# PX4FMUv2_4_6_04.net
KiCad netlist of a schematic drawn in Altium Designer
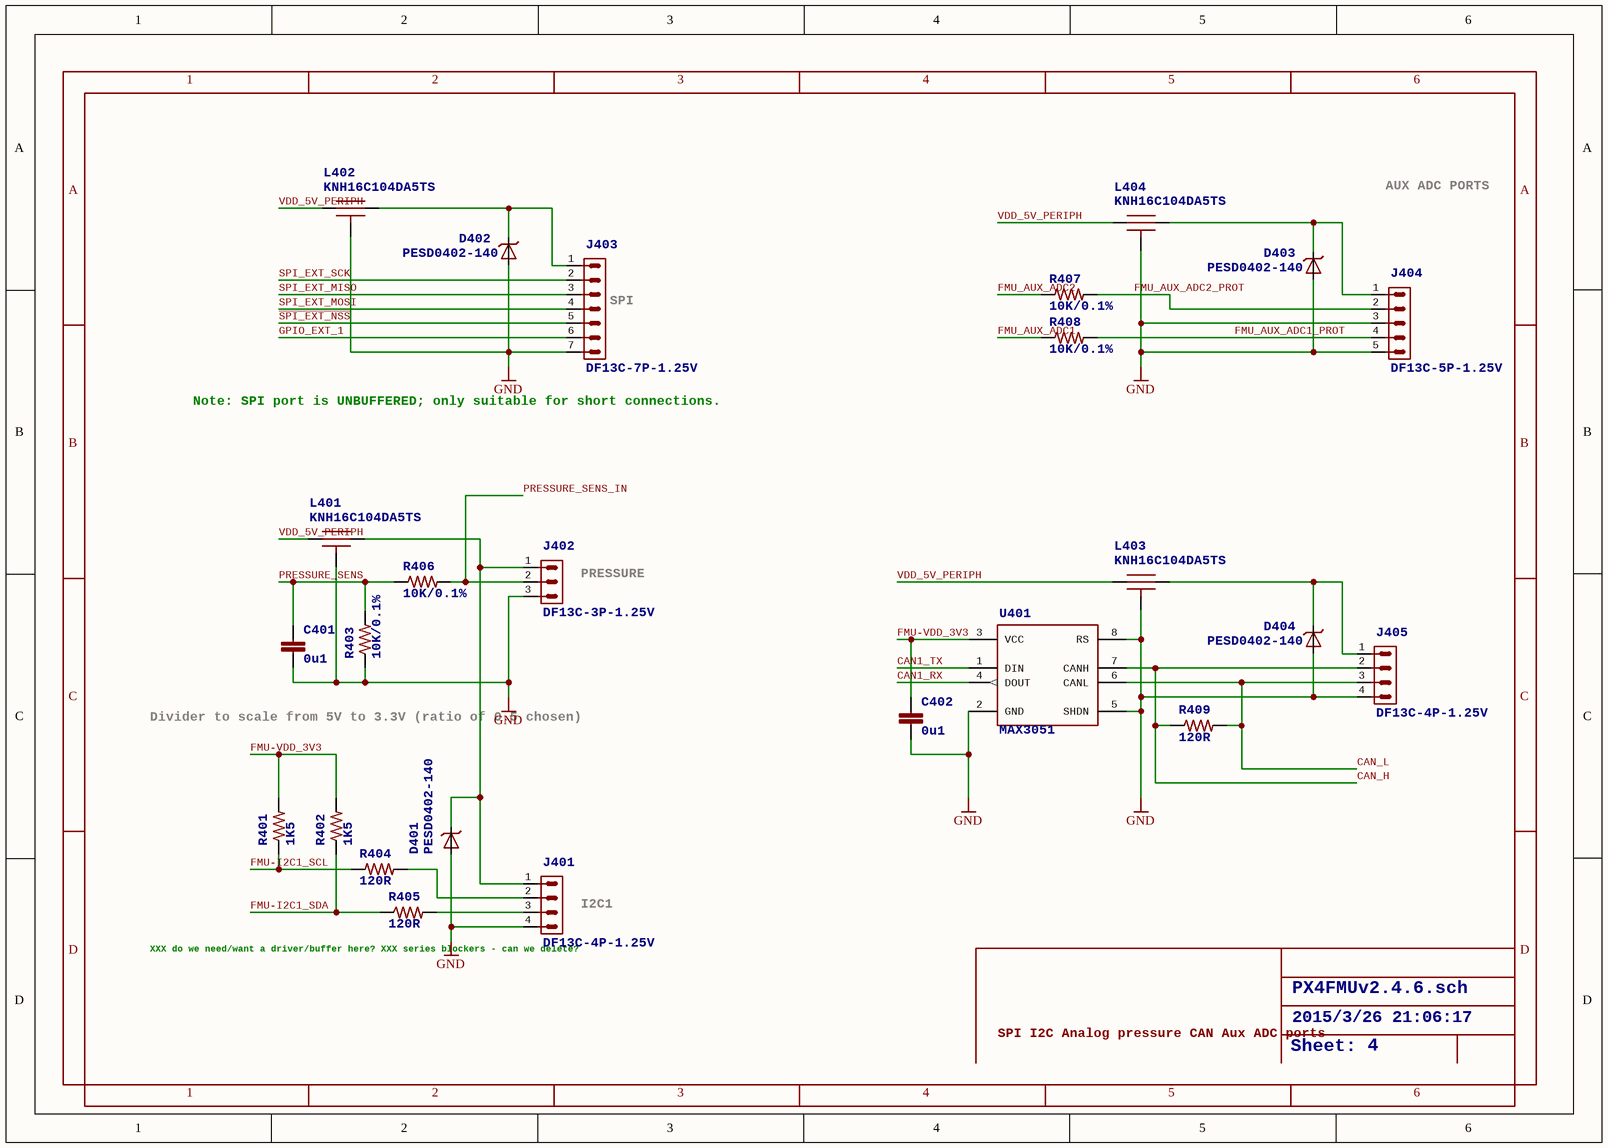
[diagram p0: PX4FMUv2.4.6_04.SchDoc]

(export (version "E")
  (design (tool "Eeschema 10.0.6"))
  (components
    (comp (ref "C401")
      (value "0u1")
      (footprint "0402-CAP")
      (description "<b>Capacitor</b>\nStandard 0603 ceramic capacitor, and 0.1\" leaded capacitor.")
      (fields (field (name "PARTNO") "CC0402ZRY5V7BB104"))
      (libsource (lib "pixhawk2") (part "CAP0402"))
    )
    (comp (ref "C402")
      (value "0u1")
      (footprint "0402-CAP")
      (description "<b>Capacitor</b>\nStandard 0603 ceramic capacitor, and 0.1\" leaded capacitor.")
      (fields (field (name "PARTNO") "CC0402ZRY5V7BB104"))
      (libsource (lib "pixhawk2") (part "CAP0402"))
    )
    (comp (ref "D401")
      (value "PESD0402-140")
      (footprint "0402-TVS")
      (libsource (lib "pixhawk2") (part "DIODE-TVS"))
    )
    (comp (ref "D402")
      (value "PESD0402-140")
      (footprint "0402-TVS")
      (libsource (lib "pixhawk2") (part "DIODE-TVS"))
    )
    (comp (ref "D403")
      (value "PESD0402-140")
      (footprint "0402-TVS")
      (libsource (lib "pixhawk2") (part "DIODE-TVS"))
    )
    (comp (ref "D404")
      (value "PESD0402-140")
      (footprint "0402-TVS")
      (libsource (lib "pixhawk2") (part "DIODE-TVS"))
    )
    (comp (ref "J401")
      (value "DF13C-4P-1.25V")
      (footprint "DF13C-4P-1.25V")
      (description "DF13-4P\n1.25mm Pitch Miniature Crimping Connector.")
      (fields (field (name "PARTNO") "DF13C-4P-1.25V(20)"))
      (libsource (lib "con-hirose-df13") (part "DF13-4P-1.25V"))
    )
    (comp (ref "J402")
      (value "DF13C-3P-1.25V")
      (footprint "DF13C-3P-1.25V")
      (description "DF13-3P\n1.25mm Pitch Miniature Crimping Connector.")
      (fields (field (name "PARTNO") "DF13C-3P-1.25V(20)"))
      (libsource (lib "con-hirose-df13") (part "DF13-3P-1.25V"))
    )
    (comp (ref "J403")
      (value "DF13C-7P-1.25V")
      (footprint "DF13C-7P-1.25V")
      (description "DF13-7P\n1.25mm Pitch Miniature Crimping Connector.")
      (fields (field (name "PARTNO") "DF13C-7P-1.25V(20)"))
      (libsource (lib "con-hirose-df13") (part "DF13-7P-1.25V"))
    )
    (comp (ref "J404")
      (value "DF13C-5P-1.25V")
      (footprint "DF13C-5P-1.25V")
      (description "DF13-5P\n1.25mm Pitch Miniature Crimping Connector.")
      (fields (field (name "PARTNO") "DF13C-5P-1.25V(20)"))
      (libsource (lib "con-hirose-df13") (part "DF13-5P-1.25V"))
    )
    (comp (ref "J405")
      (value "DF13C-4P-1.25V")
      (footprint "DF13C-4P-1.25V")
      (description "DF13-4P\n1.25mm Pitch Miniature Crimping Connector.")
      (fields (field (name "PARTNO") "DF13C-4P-1.25V(20)"))
      (libsource (lib "con-hirose-df13") (part "DF13-4P-1.25V"))
    )
    (comp (ref "L401")
      (value "KNH16C104DA5TS")
      (footprint "KYOCERA-KNH16-DA")
      (description "Kyocera KNH16C104DA5TS EMI filter")
      (libsource (lib "pixhawk2") (part "KNH16C104DA5TS"))
    )
    (comp (ref "L402")
      (value "KNH16C104DA5TS")
      (footprint "KYOCERA-KNH16-DA")
      (description "Kyocera KNH16C104DA5TS EMI filter")
      (libsource (lib "pixhawk2") (part "KNH16C104DA5TS"))
    )
    (comp (ref "L403")
      (value "KNH16C104DA5TS")
      (footprint "KYOCERA-KNH16-DA")
      (description "Kyocera KNH16C104DA5TS EMI filter")
      (libsource (lib "pixhawk2") (part "KNH16C104DA5TS"))
    )
    (comp (ref "L404")
      (value "KNH16C104DA5TS")
      (footprint "KYOCERA-KNH16-DA")
      (description "Kyocera KNH16C104DA5TS EMI filter")
      (libsource (lib "pixhawk2") (part "KNH16C104DA5TS"))
    )
    (comp (ref "R401")
      (value "1K5")
      (footprint "0402-RES")
      (fields (field (name "PARTNO") "RC0402FR-071K5L"))
      (libsource (lib "pixhawk2") (part "RESISTOR0402-RES"))
    )
    (comp (ref "R402")
      (value "1K5")
      (footprint "0402-RES")
      (fields (field (name "PARTNO") "RC0402FR-071K5L"))
      (libsource (lib "pixhawk2") (part "RESISTOR0402-RES"))
    )
    (comp (ref "R403")
      (value "10K/0.1%")
      (footprint "0402-RES")
      (fields (field (name "PARTNO") "ERA-2AEB103X"))
      (libsource (lib "pixhawk2") (part "RESISTOR0402-RES"))
    )
    (comp (ref "R404")
      (value "120R")
      (footprint "0402-RES")
      (fields (field (name "PARTNO") "RC0402FR-07120RL"))
      (libsource (lib "pixhawk2") (part "RESISTOR0402-RES"))
    )
    (comp (ref "R405")
      (value "120R")
      (footprint "0402-RES")
      (fields (field (name "PARTNO") "RC0402FR-07120RL"))
      (libsource (lib "pixhawk2") (part "RESISTOR0402-RES"))
    )
    (comp (ref "R406")
      (value "10K/0.1%")
      (footprint "0402-RES")
      (fields (field (name "PARTNO") "ERA-2AEB103X"))
      (libsource (lib "pixhawk2") (part "RESISTOR0402-RES"))
    )
    (comp (ref "R407")
      (value "10K/0.1%")
      (footprint "0402-RES")
      (fields (field (name "PARTNO") "ERA-2AEB103X"))
      (libsource (lib "pixhawk2") (part "RESISTOR0402-RES"))
    )
    (comp (ref "R408")
      (value "10K/0.1%")
      (footprint "0402-RES")
      (fields (field (name "PARTNO") "ERA-2AEB103X"))
      (libsource (lib "pixhawk2") (part "RESISTOR0402-RES"))
    )
    (comp (ref "R409")
      (value "120R")
      (footprint "0402-RES")
      (fields (field (name "PARTNO") "RC0402FR-07120RL"))
      (libsource (lib "pixhawk2") (part "RESISTOR0402-RES"))
    )
    (comp (ref "U401")
      (value "MAX3051")
      (footprint "SOT23-8")
      (description "3.3-V CAN TRANSCEIVER")
      (fields (field (name "PARTNO") "MAX3051EKA"))
      (libsource (lib "pixhawk2") (part "MAX3051MAX3051EKA"))
    )
  )
  (nets
    (net (code "1") (name "/CAN1_RX") (class "Default")
      (node (ref "U401") (pin "4") (pinfunction "DOUT_4") (pintype "output"))
    )
    (net (code "2") (name "/CAN1_TX") (class "Default")
      (node (ref "U401") (pin "1") (pinfunction "DIN_1") (pintype "passive"))
    )
    (net (code "3") (name "/CAN_H") (class "Default")
      (node (ref "J405") (pin "2") (pinfunction "2_2") (pintype "passive"))
      (node (ref "R409") (pin "P$1") (pinfunction "1_P$1") (pintype "passive"))
      (node (ref "U401") (pin "7") (pinfunction "CANH_7") (pintype "passive"))
    )
    (net (code "4") (name "/CAN_L") (class "Default")
      (node (ref "J405") (pin "3") (pinfunction "3_3") (pintype "passive"))
      (node (ref "R409") (pin "P$2") (pinfunction "2_P$2") (pintype "passive"))
      (node (ref "U401") (pin "6") (pinfunction "CANL_6") (pintype "passive"))
    )
    (net (code "5") (name "/FMU-I2C1_SCL") (class "Default")
      (node (ref "R401") (pin "P$1") (pinfunction "1_P$1") (pintype "passive"))
      (node (ref "R404") (pin "P$1") (pinfunction "1_P$1") (pintype "passive"))
    )
    (net (code "6") (name "/FMU-I2C1_SDA") (class "Default")
      (node (ref "R402") (pin "P$1") (pinfunction "1_P$1") (pintype "passive"))
      (node (ref "R405") (pin "P$1") (pinfunction "1_P$1") (pintype "passive"))
    )
    (net (code "7") (name "/FMU-VDD_3V3") (class "Default")
      (node (ref "C402") (pin "P$1") (pinfunction "1_P$1") (pintype "passive"))
      (node (ref "R401") (pin "P$2") (pinfunction "2_P$2") (pintype "passive"))
      (node (ref "R402") (pin "P$2") (pinfunction "2_P$2") (pintype "passive"))
      (node (ref "U401") (pin "3") (pinfunction "VCC_3") (pintype "passive"))
    )
    (net (code "8") (name "/FMU_AUX_ADC1") (class "Default")
      (node (ref "R408") (pin "P$1") (pinfunction "1_P$1") (pintype "passive"))
    )
    (net (code "9") (name "/FMU_AUX_ADC1_PROT") (class "Default")
      (node (ref "J404") (pin "4") (pinfunction "4_4") (pintype "passive"))
      (node (ref "R408") (pin "P$2") (pinfunction "2_P$2") (pintype "passive"))
    )
    (net (code "10") (name "/FMU_AUX_ADC2") (class "Default")
      (node (ref "R407") (pin "P$1") (pinfunction "1_P$1") (pintype "passive"))
    )
    (net (code "11") (name "/FMU_AUX_ADC2_PROT") (class "Default")
      (node (ref "J404") (pin "2") (pinfunction "2_2") (pintype "passive"))
      (node (ref "R407") (pin "P$2") (pinfunction "2_P$2") (pintype "passive"))
    )
    (net (code "12") (name "/GPIO_EXT_1") (class "Default")
      (node (ref "J403") (pin "6") (pinfunction "6_6") (pintype "passive"))
    )
    (net (code "13") (name "/PRESSURE_SENS") (class "Default")
      (node (ref "C401") (pin "P$1") (pinfunction "1_P$1") (pintype "passive"))
      (node (ref "R403") (pin "P$2") (pinfunction "2_P$2") (pintype "passive"))
      (node (ref "R406") (pin "P$1") (pinfunction "1_P$1") (pintype "passive"))
    )
    (net (code "14") (name "/PRESSURE_SENS_IN") (class "Default")
      (node (ref "J402") (pin "2") (pinfunction "2_2") (pintype "passive"))
      (node (ref "R406") (pin "P$2") (pinfunction "2_P$2") (pintype "passive"))
    )
    (net (code "15") (name "/SPI_EXT_MISO") (class "Default")
      (node (ref "J403") (pin "3") (pinfunction "3_3") (pintype "passive"))
    )
    (net (code "16") (name "/SPI_EXT_MOSI") (class "Default")
      (node (ref "J403") (pin "4") (pinfunction "4_4") (pintype "passive"))
    )
    (net (code "17") (name "/SPI_EXT_SCK") (class "Default")
      (node (ref "J403") (pin "2") (pinfunction "2_2") (pintype "passive"))
    )
    (net (code "18") (name "/VDD_5V_PERIPH") (class "Default")
      (node (ref "L401") (pin "P$1") (pinfunction "P$1_P$1") (pintype "passive"))
      (node (ref "L402") (pin "P$1") (pinfunction "P$1_P$1") (pintype "passive"))
      (node (ref "L403") (pin "P$1") (pinfunction "P$1_P$1") (pintype "passive"))
      (node (ref "L404") (pin "P$1") (pinfunction "P$1_P$1") (pintype "passive"))
    )
    (net (code "19") (name "/~{SPI_EXT_NSS}") (class "Default")
      (node (ref "J403") (pin "5") (pinfunction "5_5") (pintype "passive"))
    )
    (net (code "20") (name "GND") (class "Default")
      (node (ref "C401") (pin "P$2") (pinfunction "2_P$2") (pintype "passive"))
      (node (ref "C402") (pin "P$2") (pinfunction "2_P$2") (pintype "passive"))
      (node (ref "D401") (pin "A") (pinfunction "A_A") (pintype "passive"))
      (node (ref "D402") (pin "A") (pinfunction "A_A") (pintype "passive"))
      (node (ref "D403") (pin "A") (pinfunction "A_A") (pintype "passive"))
      (node (ref "D404") (pin "A") (pinfunction "A_A") (pintype "passive"))
      (node (ref "J401") (pin "4") (pinfunction "4_4") (pintype "passive"))
      (node (ref "J402") (pin "3") (pinfunction "3_3") (pintype "passive"))
      (node (ref "J403") (pin "7") (pinfunction "7_7") (pintype "passive"))
      (node (ref "J404") (pin "3") (pinfunction "3_3") (pintype "passive"))
      (node (ref "J404") (pin "5") (pinfunction "5_5") (pintype "passive"))
      (node (ref "J405") (pin "4") (pinfunction "4_4") (pintype "passive"))
      (node (ref "L401") (pin "P$3_P$4_P$5") (pinfunction "P$3_P$3_P$4_P$5") (pintype "passive"))
      (node (ref "L402") (pin "P$3_P$4_P$5") (pinfunction "P$3_P$3_P$4_P$5") (pintype "passive"))
      (node (ref "L403") (pin "P$3_P$4_P$5") (pinfunction "P$3_P$3_P$4_P$5") (pintype "passive"))
      (node (ref "L404") (pin "P$3_P$4_P$5") (pinfunction "P$3_P$3_P$4_P$5") (pintype "passive"))
      (node (ref "R403") (pin "P$1") (pinfunction "1_P$1") (pintype "passive"))
      (node (ref "U401") (pin "2") (pinfunction "GND_2") (pintype "open_emitter"))
      (node (ref "U401") (pin "5") (pinfunction "SHDN_5") (pintype "passive"))
      (node (ref "U401") (pin "8") (pinfunction "RS_8") (pintype "passive"))
    )
    (net (code "21") (name "Net-(D401-PadC)") (class "Default")
      (node (ref "D401") (pin "C") (pinfunction "C_C") (pintype "passive"))
      (node (ref "J401") (pin "1") (pinfunction "1_1") (pintype "passive"))
      (node (ref "J402") (pin "1") (pinfunction "1_1") (pintype "passive"))
      (node (ref "L401") (pin "P$2") (pinfunction "P$2_P$2") (pintype "passive"))
    )
    (net (code "22") (name "Net-(D402-PadC)") (class "Default")
      (node (ref "D402") (pin "C") (pinfunction "C_C") (pintype "passive"))
      (node (ref "J403") (pin "1") (pinfunction "1_1") (pintype "passive"))
      (node (ref "L402") (pin "P$2") (pinfunction "P$2_P$2") (pintype "passive"))
    )
    (net (code "23") (name "Net-(D403-PadC)") (class "Default")
      (node (ref "D403") (pin "C") (pinfunction "C_C") (pintype "passive"))
      (node (ref "J404") (pin "1") (pinfunction "1_1") (pintype "passive"))
      (node (ref "L404") (pin "P$2") (pinfunction "P$2_P$2") (pintype "passive"))
    )
    (net (code "24") (name "Net-(D404-PadC)") (class "Default")
      (node (ref "D404") (pin "C") (pinfunction "C_C") (pintype "passive"))
      (node (ref "J405") (pin "1") (pinfunction "1_1") (pintype "passive"))
      (node (ref "L403") (pin "P$2") (pinfunction "P$2_P$2") (pintype "passive"))
    )
    (net (code "25") (name "Net-(R404-2)") (class "Default")
      (node (ref "J401") (pin "2") (pinfunction "2_2") (pintype "passive"))
      (node (ref "R404") (pin "P$2") (pinfunction "2_P$2") (pintype "passive"))
    )
    (net (code "26") (name "Net-(R405-2)") (class "Default")
      (node (ref "J401") (pin "3") (pinfunction "3_3") (pintype "passive"))
      (node (ref "R405") (pin "P$2") (pinfunction "2_P$2") (pintype "passive"))
    )
  )
)
